# ReflowController_v1_1.net
KiCad netlist of a schematic drawn in EAGLE
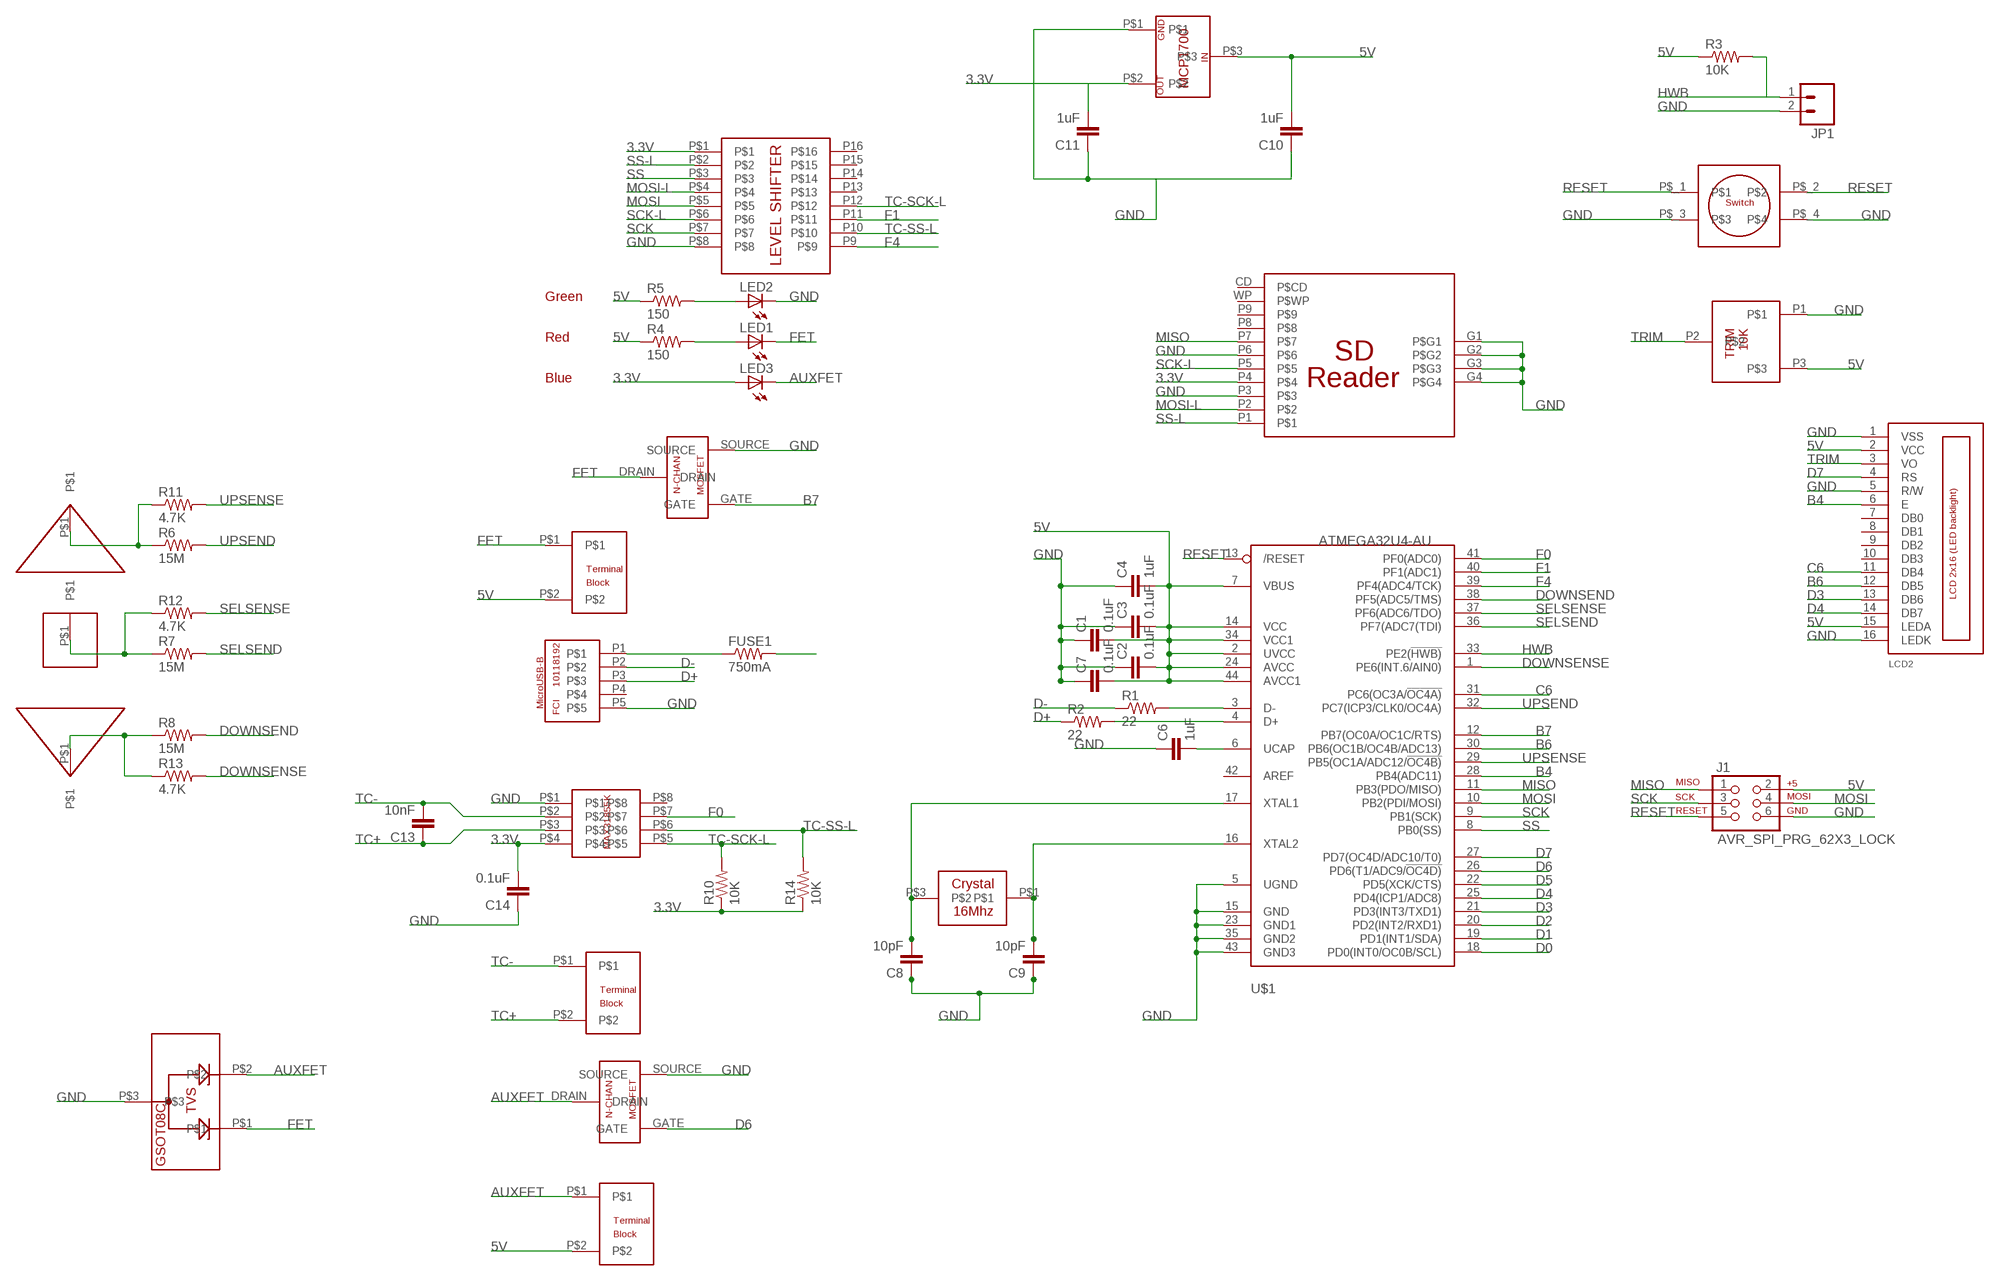
[diagram p0: schematic, sheet 1]

(export (version "E")
  (design (tool "Eeschema 10.0.6"))
  (components
    (comp (ref "C1")
      (value "0.1uF")
      (footprint "eagle-import:0603-CAP")
      (libsource (lib "eagle-import") (part "CAP0603-CAP"))
    )
    (comp (ref "C2")
      (value "0.1uF")
      (footprint "eagle-import:0603-CAP")
      (libsource (lib "eagle-import") (part "CAP0603-CAP"))
    )
    (comp (ref "C3")
      (value "0.1uF")
      (footprint "eagle-import:0603-CAP")
      (libsource (lib "eagle-import") (part "CAP0603-CAP"))
    )
    (comp (ref "C4")
      (value "1uF")
      (footprint "eagle-import:0603-CAP")
      (libsource (lib "eagle-import") (part "CAP0603-CAP"))
    )
    (comp (ref "C6")
      (value "1uF")
      (footprint "eagle-import:0603-CAP")
      (libsource (lib "eagle-import") (part "CAP0603-CAP"))
    )
    (comp (ref "C7")
      (value "0.1uF")
      (footprint "eagle-import:0603-CAP")
      (libsource (lib "eagle-import") (part "CAP0603-CAP"))
    )
    (comp (ref "C8")
      (value "10pF")
      (footprint "eagle-import:0603-CAP")
      (libsource (lib "eagle-import") (part "CAP0603-CAP"))
    )
    (comp (ref "C9")
      (value "10pF")
      (footprint "eagle-import:0603-CAP")
      (libsource (lib "eagle-import") (part "CAP0603-CAP"))
    )
    (comp (ref "C10")
      (value "1uF")
      (footprint "eagle-import:0603-CAP")
      (libsource (lib "eagle-import") (part "CAP0603-CAP"))
    )
    (comp (ref "C11")
      (value "1uF")
      (footprint "eagle-import:0603-CAP")
      (libsource (lib "eagle-import") (part "CAP0603-CAP"))
    )
    (comp (ref "C13")
      (value "10nF")
      (footprint "eagle-import:0603-CAP")
      (libsource (lib "eagle-import") (part "CAP0603-CAP"))
    )
    (comp (ref "C14")
      (value "0.1uF")
      (footprint "eagle-import:0603-CAP")
      (libsource (lib "eagle-import") (part "CAP0603-CAP"))
    )
    (comp (ref "FUSE1")
      (value "750mA")
      (footprint "eagle-import:0603-RES")
      (libsource (lib "eagle-import") (part "RESISTOR0603-RES"))
    )
    (comp (ref "J1")
      (value "AVR_SPI_PRG_62X3_LOCK")
      (footprint "eagle-import:2X3_LOCK")
      (libsource (lib "eagle-import") (part "AVR_SPI_PRG_62X3_LOCK"))
    )
    (comp (ref "JP1")
      (value "M02PTH")
      (footprint "eagle-import:1X02")
      (libsource (lib "eagle-import") (part "M02PTH"))
    )
    (comp (ref "LCD2")
      (value "LCD_2X16_SIL")
      (footprint "eagle-import:HY-1602F")
      (libsource (lib "eagle-import") (part "LCD_2X16_SIL"))
    )
    (comp (ref "LED1")
      (value "LED0603")
      (footprint "eagle-import:LED-0603")
      (libsource (lib "eagle-import") (part "LED0603"))
    )
    (comp (ref "LED2")
      (value "LED0603")
      (footprint "eagle-import:LED-0603")
      (libsource (lib "eagle-import") (part "LED0603"))
    )
    (comp (ref "LED3")
      (value "LED0603")
      (footprint "eagle-import:LED-0603")
      (libsource (lib "eagle-import") (part "LED0603"))
    )
    (comp (ref "R1")
      (value "22")
      (footprint "eagle-import:0603-RES")
      (libsource (lib "eagle-import") (part "RESISTOR0603-RES"))
    )
    (comp (ref "R2")
      (value "22")
      (footprint "eagle-import:0603-RES")
      (libsource (lib "eagle-import") (part "RESISTOR0603-RES"))
    )
    (comp (ref "R3")
      (value "10K")
      (footprint "eagle-import:0603-RES")
      (libsource (lib "eagle-import") (part "RESISTOR0603-RES"))
    )
    (comp (ref "R4")
      (value "150")
      (footprint "eagle-import:0603-RES")
      (libsource (lib "eagle-import") (part "RESISTOR0603-RES"))
    )
    (comp (ref "R5")
      (value "150")
      (footprint "eagle-import:0603-RES")
      (libsource (lib "eagle-import") (part "RESISTOR0603-RES"))
    )
    (comp (ref "R6")
      (value "15M")
      (footprint "eagle-import:0603-RES")
      (libsource (lib "eagle-import") (part "RESISTOR0603-RES"))
    )
    (comp (ref "R7")
      (value "15M")
      (footprint "eagle-import:0603-RES")
      (libsource (lib "eagle-import") (part "RESISTOR0603-RES"))
    )
    (comp (ref "R8")
      (value "15M")
      (footprint "eagle-import:0603-RES")
      (libsource (lib "eagle-import") (part "RESISTOR0603-RES"))
    )
    (comp (ref "R10")
      (value "10K")
      (footprint "eagle-import:0603-RES")
      (libsource (lib "eagle-import") (part "RESISTOR0603-RES"))
    )
    (comp (ref "R11")
      (value "4.7K")
      (footprint "eagle-import:0603-RES")
      (libsource (lib "eagle-import") (part "RESISTOR0603-RES"))
    )
    (comp (ref "R12")
      (value "4.7K")
      (footprint "eagle-import:0603-RES")
      (libsource (lib "eagle-import") (part "RESISTOR0603-RES"))
    )
    (comp (ref "R13")
      (value "4.7K")
      (footprint "eagle-import:0603-RES")
      (libsource (lib "eagle-import") (part "RESISTOR0603-RES"))
    )
    (comp (ref "R14")
      (value "10K")
      (footprint "eagle-import:0603-RES")
      (libsource (lib "eagle-import") (part "RESISTOR0603-RES"))
    )
    (comp (ref "U$1")
      (value "ATMEGA32U4-AU")
      (footprint "eagle-import:TQFP44")
      (libsource (lib "eagle-import") (part "ATMEGA32U4-AU"))
    )
    (comp (ref "U$2")
      (value "16MHZ-CRYSTAL_NX3225GA-16.000M-STD-CRG-1")
      (footprint "eagle-import:16MHZ-CRYSTAL_NX3225GA-16.000M-STD-CRG-1")
      (libsource (lib "eagle-import") (part "16MHZ-CRYSTAL_NX3225GA-16.000M-STD-CRG-1"))
    )
    (comp (ref "U$3")
      (value "USB-B_10118192-0001LF")
      (footprint "eagle-import:USB-B_10118192-0001LF")
      (libsource (lib "eagle-import") (part "USB-B_10118192-0001LF"))
    )
    (comp (ref "U$4")
      (value "SDREADER_2041021-4")
      (footprint "eagle-import:SDREADER_2041021-4")
      (libsource (lib "eagle-import") (part "SDREADER_2041021-4"))
    )
    (comp (ref "U$5")
      (value "2POS_TERM_ED2748-ND")
      (footprint "eagle-import:2POS_TERM_ED2748-ND")
      (libsource (lib "eagle-import") (part "2POS_TERM_ED2748-ND"))
    )
    (comp (ref "U$6")
      (value "N-MOSFET630_DMG1012T-7DICT-ND")
      (footprint "eagle-import:N-MOSFET630_DMG1012T-7DICT-ND")
      (libsource (lib "eagle-import") (part "N-MOSFET630_DMG1012T-7DICT-ND"))
    )
    (comp (ref "U$7")
      (value "2POS_TERM_ED2748-ND")
      (footprint "eagle-import:2POS_TERM_ED2748-ND")
      (libsource (lib "eagle-import") (part "2POS_TERM_ED2748-ND"))
    )
    (comp (ref "U$8")
      (value "NXP_LVL_SHIFT_74HC4050D,653")
      (footprint "eagle-import:NXP_LVL_SHIFT_74HC4050D,653")
      (libsource (lib "eagle-import") (part "NXP_LVL_SHIFT_74HC4050D,653"))
    )
    (comp (ref "U$9")
      (value "MAX_TC_MAX31855KASA+")
      (footprint "eagle-import:MAX_TC_MAX31855KASA+")
      (libsource (lib "eagle-import") (part "MAX_TC_MAX31855KASA+"))
    )
    (comp (ref "U$10")
      (value "10K_TRIM_3362F-1-103LF")
      (footprint "eagle-import:10K_TRIM_3362F-1-103LF")
      (libsource (lib "eagle-import") (part "10K_TRIM_3362F-1-103LF"))
    )
    (comp (ref "U$11")
      (value "MCP1700__LDO")
      (footprint "eagle-import:MCP1700__LDO")
      (libsource (lib "eagle-import") (part "MCP1700__LDO"))
    )
    (comp (ref "U$12")
      (value "MOM-SWITCH-EG4620CT-ND")
      (footprint "eagle-import:MOM-SWITCH-EG4620CT-ND")
      (libsource (lib "eagle-import") (part "MOM-SWITCH-EG4620CT-ND"))
    )
    (comp (ref "U$13")
      (value "CAPTOUCH_ARROW")
      (footprint "eagle-import:CAPTOUCH_ARROW")
      (libsource (lib "eagle-import") (part "CAPTOUCH_ARROW"))
    )
    (comp (ref "U$14")
      (value "CAPTOUCH_ARROW")
      (footprint "eagle-import:CAPTOUCH_ARROW")
      (libsource (lib "eagle-import") (part "CAPTOUCH_ARROW"))
    )
    (comp (ref "U$15")
      (value "CAPTOUCH_SQUARE")
      (footprint "eagle-import:CAPTOUCH_SQUARE")
      (libsource (lib "eagle-import") (part "CAPTOUCH_SQUARE"))
    )
    (comp (ref "U$16")
      (value "N-MOSFET630_DMG1012T-7DICT-ND")
      (footprint "eagle-import:N-MOSFET630_DMG1012T-7DICT-ND")
      (libsource (lib "eagle-import") (part "N-MOSFET630_DMG1012T-7DICT-ND"))
    )
    (comp (ref "U$17")
      (value "2POS_TERM_ED2748-ND")
      (footprint "eagle-import:2POS_TERM_ED2748-ND")
      (libsource (lib "eagle-import") (part "2POS_TERM_ED2748-ND"))
    )
    (comp (ref "U$18")
      (value "TVS_DIODE_MATRIX_GSOT08C-GS08")
      (footprint "eagle-import:TVS_DIODE_MATRIX_GSOT08C-GS08")
      (libsource (lib "eagle-import") (part "TVS_DIODE_MATRIX_GSOT08C-GS08"))
    )
  )
  (nets
    (net (code "1") (name "/3.3V") (class "Default")
      (node (ref "C11") (pin "2") (pinfunction "2_2") (pintype "passive"))
      (node (ref "C14") (pin "2") (pinfunction "2_2") (pintype "passive"))
      (node (ref "LED3") (pin "A") (pinfunction "A_A") (pintype "passive"))
      (node (ref "R10") (pin "1") (pinfunction "1_1") (pintype "passive"))
      (node (ref "R14") (pin "1") (pinfunction "1_1") (pintype "passive"))
      (node (ref "U$11") (pin "P$2") (pinfunction "P$2_P$2") (pintype "bidirectional"))
      (node (ref "U$4") (pin "P4") (pinfunction "P$4_P4") (pintype "bidirectional"))
      (node (ref "U$8") (pin "P$1") (pinfunction "P$1_P$1") (pintype "bidirectional"))
      (node (ref "U$9") (pin "P$4") (pinfunction "P$4_P$4") (pintype "bidirectional"))
    )
    (net (code "2") (name "/5V") (class "Default")
      (node (ref "C1") (pin "2") (pinfunction "2_2") (pintype "passive"))
      (node (ref "C10") (pin "2") (pinfunction "2_2") (pintype "passive"))
      (node (ref "C2") (pin "2") (pinfunction "2_2") (pintype "passive"))
      (node (ref "C3") (pin "2") (pinfunction "2_2") (pintype "passive"))
      (node (ref "C4") (pin "2") (pinfunction "2_2") (pintype "passive"))
      (node (ref "C7") (pin "2") (pinfunction "2_2") (pintype "passive"))
      (node (ref "FUSE1") (pin "2") (pinfunction "2_2") (pintype "passive"))
      (node (ref "J1") (pin "2") (pinfunction "2_2") (pintype "passive"))
      (node (ref "LCD2") (pin "15") (pinfunction "LEDA_15") (pintype "passive"))
      (node (ref "LCD2") (pin "2") (pinfunction "VCC_2") (pintype "power_in"))
      (node (ref "R3") (pin "1") (pinfunction "1_1") (pintype "passive"))
      (node (ref "R4") (pin "1") (pinfunction "1_1") (pintype "passive"))
      (node (ref "R5") (pin "1") (pinfunction "1_1") (pintype "passive"))
      (node (ref "U$1") (pin "14") (pinfunction "VCC_14") (pintype "bidirectional"))
      (node (ref "U$1") (pin "2") (pinfunction "UVCC_2") (pintype "bidirectional"))
      (node (ref "U$1") (pin "24") (pinfunction "AVCC_24") (pintype "bidirectional"))
      (node (ref "U$1") (pin "34") (pinfunction "VCC1_34") (pintype "bidirectional"))
      (node (ref "U$1") (pin "44") (pinfunction "AVCC1_44") (pintype "bidirectional"))
      (node (ref "U$1") (pin "7") (pinfunction "VBUS_7") (pintype "bidirectional"))
      (node (ref "U$10") (pin "P3") (pinfunction "P$3_P3") (pintype "bidirectional"))
      (node (ref "U$11") (pin "P$3") (pinfunction "P$3_P$3") (pintype "bidirectional"))
      (node (ref "U$17") (pin "P$2") (pinfunction "P$2_P$2") (pintype "bidirectional"))
      (node (ref "U$5") (pin "P$2") (pinfunction "P$2_P$2") (pintype "bidirectional"))
    )
    (net (code "3") (name "/AUXFET") (class "Default")
      (node (ref "LED3") (pin "C") (pinfunction "C_C") (pintype "passive"))
      (node (ref "U$16") (pin "DRAIN") (pinfunction "DRAIN_DRAIN") (pintype "bidirectional"))
      (node (ref "U$17") (pin "P$1") (pinfunction "P$1_P$1") (pintype "bidirectional"))
      (node (ref "U$18") (pin "P$2") (pinfunction "P$2_P$2") (pintype "bidirectional"))
    )
    (net (code "4") (name "/B4") (class "Default")
      (node (ref "LCD2") (pin "6") (pinfunction "E_6") (pintype "input"))
      (node (ref "U$1") (pin "28") (pinfunction "PB4(ADC11)_28") (pintype "bidirectional"))
    )
    (net (code "5") (name "/B6") (class "Default")
      (node (ref "LCD2") (pin "12") (pinfunction "DB5_12") (pintype "bidirectional"))
      (node (ref "U$1") (pin "30") (pinfunction "PB6(OC1B/OC4B/ADC13)_30") (pintype "bidirectional"))
    )
    (net (code "6") (name "/B7") (class "Default")
      (node (ref "U$1") (pin "12") (pinfunction "PB7(OC0A/OC1C/RTS)_12") (pintype "bidirectional"))
      (node (ref "U$6") (pin "GATE") (pinfunction "GATE_GATE") (pintype "bidirectional"))
    )
    (net (code "7") (name "/C6") (class "Default")
      (node (ref "LCD2") (pin "11") (pinfunction "DB4_11") (pintype "bidirectional"))
      (node (ref "U$1") (pin "31") (pinfunction "PC6(OC3A/~{OC4A})_31") (pintype "bidirectional"))
    )
    (net (code "8") (name "/D+") (class "Default")
      (node (ref "R2") (pin "1") (pinfunction "1_1") (pintype "passive"))
      (node (ref "U$3") (pin "P3") (pinfunction "P$3_P3") (pintype "bidirectional"))
    )
    (net (code "9") (name "/D-") (class "Default")
      (node (ref "R1") (pin "1") (pinfunction "1_1") (pintype "passive"))
      (node (ref "U$3") (pin "P2") (pinfunction "P$2_P2") (pintype "bidirectional"))
    )
    (net (code "10") (name "/D0") (class "Default")
      (node (ref "U$1") (pin "18") (pinfunction "PD0(INT0/OC0B/SCL)_18") (pintype "bidirectional"))
    )
    (net (code "11") (name "/D1") (class "Default")
      (node (ref "U$1") (pin "19") (pinfunction "PD1(INT1/SDA)_19") (pintype "bidirectional"))
    )
    (net (code "12") (name "/D2") (class "Default")
      (node (ref "U$1") (pin "20") (pinfunction "PD2(INT2/RXD1)_20") (pintype "bidirectional"))
    )
    (net (code "13") (name "/D3") (class "Default")
      (node (ref "LCD2") (pin "13") (pinfunction "DB6_13") (pintype "bidirectional"))
      (node (ref "U$1") (pin "21") (pinfunction "PD3(INT3/TXD1)_21") (pintype "bidirectional"))
    )
    (net (code "14") (name "/D4") (class "Default")
      (node (ref "LCD2") (pin "14") (pinfunction "DB7_14") (pintype "bidirectional"))
      (node (ref "U$1") (pin "25") (pinfunction "PD4(ICP1/ADC8)_25") (pintype "bidirectional"))
    )
    (net (code "15") (name "/D5") (class "Default")
      (node (ref "U$1") (pin "22") (pinfunction "PD5(XCK/CTS)_22") (pintype "bidirectional"))
    )
    (net (code "16") (name "/D6") (class "Default")
      (node (ref "U$1") (pin "26") (pinfunction "PD6(T1/ADC9/~{OC4D})_26") (pintype "bidirectional"))
      (node (ref "U$16") (pin "GATE") (pinfunction "GATE_GATE") (pintype "bidirectional"))
    )
    (net (code "17") (name "/D7") (class "Default")
      (node (ref "LCD2") (pin "4") (pinfunction "RS_4") (pintype "input"))
      (node (ref "U$1") (pin "27") (pinfunction "PD7(OC4D/ADC10/T0)_27") (pintype "bidirectional"))
    )
    (net (code "18") (name "/DOWNSEND") (class "Default")
      (node (ref "R8") (pin "2") (pinfunction "2_2") (pintype "passive"))
      (node (ref "U$1") (pin "38") (pinfunction "PF5(ADC5/TMS)_38") (pintype "bidirectional"))
    )
    (net (code "19") (name "/DOWNSENSE") (class "Default")
      (node (ref "R13") (pin "2") (pinfunction "2_2") (pintype "passive"))
      (node (ref "U$1") (pin "1") (pinfunction "PE6(INT.6/AIN0)_1") (pintype "bidirectional"))
    )
    (net (code "20") (name "/F0") (class "Default")
      (node (ref "U$1") (pin "41") (pinfunction "PF0(ADC0)_41") (pintype "bidirectional"))
      (node (ref "U$9") (pin "P$7") (pinfunction "P$7_P$7") (pintype "bidirectional"))
    )
    (net (code "21") (name "/F1") (class "Default")
      (node (ref "U$1") (pin "40") (pinfunction "PF1(ADC1)_40") (pintype "bidirectional"))
      (node (ref "U$8") (pin "P11") (pinfunction "P$11_P11") (pintype "bidirectional"))
    )
    (net (code "22") (name "/F4") (class "Default")
      (node (ref "U$1") (pin "39") (pinfunction "PF4(ADC4/TCK)_39") (pintype "bidirectional"))
      (node (ref "U$8") (pin "P9") (pinfunction "P$9_P9") (pintype "bidirectional"))
    )
    (net (code "23") (name "/FET") (class "Default")
      (node (ref "LED1") (pin "C") (pinfunction "C_C") (pintype "passive"))
      (node (ref "U$18") (pin "P$1") (pinfunction "P$1_P$1") (pintype "bidirectional"))
      (node (ref "U$5") (pin "P$1") (pinfunction "P$1_P$1") (pintype "bidirectional"))
      (node (ref "U$6") (pin "DRAIN") (pinfunction "DRAIN_DRAIN") (pintype "bidirectional"))
    )
    (net (code "24") (name "/GND") (class "Default")
      (node (ref "C1") (pin "1") (pinfunction "1_1") (pintype "passive"))
      (node (ref "C10") (pin "1") (pinfunction "1_1") (pintype "passive"))
      (node (ref "C11") (pin "1") (pinfunction "1_1") (pintype "passive"))
      (node (ref "C14") (pin "1") (pinfunction "1_1") (pintype "passive"))
      (node (ref "C2") (pin "1") (pinfunction "1_1") (pintype "passive"))
      (node (ref "C3") (pin "1") (pinfunction "1_1") (pintype "passive"))
      (node (ref "C4") (pin "1") (pinfunction "1_1") (pintype "passive"))
      (node (ref "C6") (pin "1") (pinfunction "1_1") (pintype "passive"))
      (node (ref "C7") (pin "1") (pinfunction "1_1") (pintype "passive"))
      (node (ref "C8") (pin "1") (pinfunction "1_1") (pintype "passive"))
      (node (ref "C9") (pin "1") (pinfunction "1_1") (pintype "passive"))
      (node (ref "J1") (pin "6") (pinfunction "6_6") (pintype "passive"))
      (node (ref "JP1") (pin "2") (pinfunction "2_2") (pintype "passive"))
      (node (ref "LCD2") (pin "1") (pinfunction "VSS_1") (pintype "power_in"))
      (node (ref "LCD2") (pin "16") (pinfunction "LEDK_16") (pintype "passive"))
      (node (ref "LCD2") (pin "5") (pinfunction "R/W_5") (pintype "input"))
      (node (ref "LED2") (pin "C") (pinfunction "C_C") (pintype "passive"))
      (node (ref "U$1") (pin "15") (pinfunction "GND_15") (pintype "bidirectional"))
      (node (ref "U$1") (pin "23") (pinfunction "GND1_23") (pintype "bidirectional"))
      (node (ref "U$1") (pin "35") (pinfunction "GND2_35") (pintype "bidirectional"))
      (node (ref "U$1") (pin "43") (pinfunction "GND3_43") (pintype "bidirectional"))
      (node (ref "U$1") (pin "5") (pinfunction "UGND_5") (pintype "bidirectional"))
      (node (ref "U$10") (pin "P1") (pinfunction "P$1_P1") (pintype "bidirectional"))
      (node (ref "U$11") (pin "P$1") (pinfunction "P$1_P$1") (pintype "bidirectional"))
      (node (ref "U$12") (pin "P$_3") (pinfunction "P$3_P$_3") (pintype "bidirectional"))
      (node (ref "U$12") (pin "P$_4") (pinfunction "P$4_P$_4") (pintype "bidirectional"))
      (node (ref "U$16") (pin "SOURCE") (pinfunction "SOURCE_SOURCE") (pintype "bidirectional"))
      (node (ref "U$18") (pin "P$3") (pinfunction "P$3_P$3") (pintype "bidirectional"))
      (node (ref "U$3") (pin "P5") (pinfunction "P$5_P5") (pintype "bidirectional"))
      (node (ref "U$4") (pin "G1") (pinfunction "P$G1_G1") (pintype "bidirectional"))
      (node (ref "U$4") (pin "G2") (pinfunction "P$G2_G2") (pintype "bidirectional"))
      (node (ref "U$4") (pin "G3") (pinfunction "P$G3_G3") (pintype "bidirectional"))
      (node (ref "U$4") (pin "G4") (pinfunction "P$G4_G4") (pintype "bidirectional"))
      (node (ref "U$4") (pin "P3") (pinfunction "P$3_P3") (pintype "bidirectional"))
      (node (ref "U$4") (pin "P6") (pinfunction "P$6_P6") (pintype "bidirectional"))
      (node (ref "U$6") (pin "SOURCE") (pinfunction "SOURCE_SOURCE") (pintype "bidirectional"))
      (node (ref "U$8") (pin "P$8") (pinfunction "P$8_P$8") (pintype "bidirectional"))
      (node (ref "U$9") (pin "P$1") (pinfunction "P$1_P$1") (pintype "bidirectional"))
    )
    (net (code "25") (name "/HWB") (class "Default")
      (node (ref "JP1") (pin "1") (pinfunction "1_1") (pintype "passive"))
      (node (ref "R3") (pin "2") (pinfunction "2_2") (pintype "passive"))
      (node (ref "U$1") (pin "33") (pinfunction "PE2(~{HWB})_33") (pintype "bidirectional"))
    )
    (net (code "26") (name "/MISO") (class "Default")
      (node (ref "J1") (pin "1") (pinfunction "1_1") (pintype "passive"))
      (node (ref "U$1") (pin "11") (pinfunction "PB3(PDO/MISO)_11") (pintype "bidirectional"))
      (node (ref "U$4") (pin "P7") (pinfunction "P$7_P7") (pintype "bidirectional"))
    )
    (net (code "27") (name "/MOSI") (class "Default")
      (node (ref "J1") (pin "4") (pinfunction "4_4") (pintype "passive"))
      (node (ref "U$1") (pin "10") (pinfunction "PB2(PDI/MOSI)_10") (pintype "bidirectional"))
      (node (ref "U$8") (pin "P$5") (pinfunction "P$5_P$5") (pintype "bidirectional"))
    )
    (net (code "28") (name "/MOSI-L") (class "Default")
      (node (ref "U$4") (pin "P2") (pinfunction "P$2_P2") (pintype "bidirectional"))
      (node (ref "U$8") (pin "P$4") (pinfunction "P$4_P$4") (pintype "bidirectional"))
    )
    (net (code "29") (name "/RESET") (class "Default")
      (node (ref "J1") (pin "5") (pinfunction "5_5") (pintype "passive"))
      (node (ref "U$1") (pin "13") (pinfunction "/RESET_13") (pintype "bidirectional"))
      (node (ref "U$12") (pin "P$_1") (pinfunction "P$1_P$_1") (pintype "bidirectional"))
      (node (ref "U$12") (pin "P$_2") (pinfunction "P$2_P$_2") (pintype "bidirectional"))
    )
    (net (code "30") (name "/SCK") (class "Default")
      (node (ref "J1") (pin "3") (pinfunction "3_3") (pintype "passive"))
      (node (ref "U$1") (pin "9") (pinfunction "PB1(SCK)_9") (pintype "bidirectional"))
      (node (ref "U$8") (pin "P$7") (pinfunction "P$7_P$7") (pintype "bidirectional"))
    )
    (net (code "31") (name "/SCK-L") (class "Default")
      (node (ref "U$4") (pin "P5") (pinfunction "P$5_P5") (pintype "bidirectional"))
      (node (ref "U$8") (pin "P$6") (pinfunction "P$6_P$6") (pintype "bidirectional"))
    )
    (net (code "32") (name "/SELSEND") (class "Default")
      (node (ref "R7") (pin "2") (pinfunction "2_2") (pintype "passive"))
      (node (ref "U$1") (pin "36") (pinfunction "PF7(ADC7(TDI)_36") (pintype "bidirectional"))
    )
    (net (code "33") (name "/SELSENSE") (class "Default")
      (node (ref "R12") (pin "2") (pinfunction "2_2") (pintype "passive"))
      (node (ref "U$1") (pin "37") (pinfunction "PF6(ADC6/TDO)_37") (pintype "bidirectional"))
    )
    (net (code "34") (name "/SS") (class "Default")
      (node (ref "U$1") (pin "8") (pinfunction "PB0(SS)_8") (pintype "bidirectional"))
      (node (ref "U$8") (pin "P$3") (pinfunction "P$3_P$3") (pintype "bidirectional"))
    )
    (net (code "35") (name "/SS-L") (class "Default")
      (node (ref "U$4") (pin "P1") (pinfunction "P$1_P1") (pintype "bidirectional"))
      (node (ref "U$8") (pin "P$2") (pinfunction "P$2_P$2") (pintype "bidirectional"))
    )
    (net (code "36") (name "/TC+") (class "Default")
      (node (ref "C13") (pin "1") (pinfunction "1_1") (pintype "passive"))
      (node (ref "U$7") (pin "P$2") (pinfunction "P$2_P$2") (pintype "bidirectional"))
      (node (ref "U$9") (pin "P$3") (pinfunction "P$3_P$3") (pintype "bidirectional"))
    )
    (net (code "37") (name "/TC-") (class "Default")
      (node (ref "C13") (pin "2") (pinfunction "2_2") (pintype "passive"))
      (node (ref "U$7") (pin "P$1") (pinfunction "P$1_P$1") (pintype "bidirectional"))
      (node (ref "U$9") (pin "P$2") (pinfunction "P$2_P$2") (pintype "bidirectional"))
    )
    (net (code "38") (name "/TC-SCK-L") (class "Default")
      (node (ref "R10") (pin "2") (pinfunction "2_2") (pintype "passive"))
      (node (ref "U$8") (pin "P12") (pinfunction "P$12_P12") (pintype "bidirectional"))
      (node (ref "U$9") (pin "P$5") (pinfunction "P$5_P$5") (pintype "bidirectional"))
    )
    (net (code "39") (name "/TC-SS-L") (class "Default")
      (node (ref "R14") (pin "2") (pinfunction "2_2") (pintype "passive"))
      (node (ref "U$8") (pin "P10") (pinfunction "P$10_P10") (pintype "bidirectional"))
      (node (ref "U$9") (pin "P$6") (pinfunction "P$6_P$6") (pintype "bidirectional"))
    )
    (net (code "40") (name "/TRIM") (class "Default")
      (node (ref "LCD2") (pin "3") (pinfunction "VO_3") (pintype "input"))
      (node (ref "U$10") (pin "P2") (pinfunction "P$2_P2") (pintype "bidirectional"))
    )
    (net (code "41") (name "/UPSEND") (class "Default")
      (node (ref "R6") (pin "2") (pinfunction "2_2") (pintype "passive"))
      (node (ref "U$1") (pin "32") (pinfunction "PC7(ICP3/CLK0/OC4A)_32") (pintype "bidirectional"))
    )
    (net (code "42") (name "/UPSENSE") (class "Default")
      (node (ref "R11") (pin "2") (pinfunction "2_2") (pintype "passive"))
      (node (ref "U$1") (pin "29") (pinfunction "PB5(OC1A/ADC12/~{OC4B})_29") (pintype "bidirectional"))
    )
    (net (code "43") (name "Net-(LED1-PadA)") (class "Default")
      (node (ref "LED1") (pin "A") (pinfunction "A_A") (pintype "passive"))
      (node (ref "R4") (pin "2") (pinfunction "2_2") (pintype "passive"))
    )
    (net (code "44") (name "Net-(LED2-PadA)") (class "Default")
      (node (ref "LED2") (pin "A") (pinfunction "A_A") (pintype "passive"))
      (node (ref "R5") (pin "2") (pinfunction "2_2") (pintype "passive"))
    )
    (net (code "45") (name "Net-(R11-Pad1)") (class "Default")
      (node (ref "R11") (pin "1") (pinfunction "1_1") (pintype "passive"))
      (node (ref "R6") (pin "1") (pinfunction "1_1") (pintype "passive"))
      (node (ref "U$13") (pin "P$1") (pinfunction "P$1_P$1") (pintype "bidirectional"))
    )
    (net (code "46") (name "Net-(R12-Pad1)") (class "Default")
      (node (ref "R12") (pin "1") (pinfunction "1_1") (pintype "passive"))
      (node (ref "R7") (pin "1") (pinfunction "1_1") (pintype "passive"))
      (node (ref "U$15") (pin "P$1") (pinfunction "P$1_P$1") (pintype "bidirectional"))
    )
    (net (code "47") (name "Net-(R13-Pad1)") (class "Default")
      (node (ref "R13") (pin "1") (pinfunction "1_1") (pintype "passive"))
      (node (ref "R8") (pin "1") (pinfunction "1_1") (pintype "passive"))
      (node (ref "U$14") (pin "P$1") (pinfunction "P$1_P$1") (pintype "bidirectional"))
    )
    (net (code "48") (name "Net-(U$1-D+)") (class "Default")
      (node (ref "R2") (pin "2") (pinfunction "2_2") (pintype "passive"))
      (node (ref "U$1") (pin "4") (pinfunction "D+_4") (pintype "bidirectional"))
    )
    (net (code "49") (name "Net-(U$1-D-)") (class "Default")
      (node (ref "R1") (pin "2") (pinfunction "2_2") (pintype "passive"))
      (node (ref "U$1") (pin "3") (pinfunction "D-_3") (pintype "bidirectional"))
    )
    (net (code "50") (name "Net-(U$1-UCAP)") (class "Default")
      (node (ref "C6") (pin "2") (pinfunction "2_2") (pintype "passive"))
      (node (ref "U$1") (pin "6") (pinfunction "UCAP_6") (pintype "bidirectional"))
    )
    (net (code "51") (name "Net-(U$1-XTAL1)") (class "Default")
      (node (ref "C8") (pin "2") (pinfunction "2_2") (pintype "passive"))
      (node (ref "U$1") (pin "17") (pinfunction "XTAL1_17") (pintype "bidirectional"))
      (node (ref "U$2") (pin "P$3") (pinfunction "P$2_P$3") (pintype "bidirectional"))
    )
    (net (code "52") (name "Net-(U$1-XTAL2)") (class "Default")
      (node (ref "C9") (pin "2") (pinfunction "2_2") (pintype "passive"))
      (node (ref "U$1") (pin "16") (pinfunction "XTAL2_16") (pintype "bidirectional"))
      (node (ref "U$2") (pin "P$1") (pinfunction "P$1_P$1") (pintype "bidirectional"))
    )
    (net (code "53") (name "Net-(U$3-P$1)") (class "Default")
      (node (ref "FUSE1") (pin "1") (pinfunction "1_1") (pintype "passive"))
      (node (ref "U$3") (pin "P1") (pinfunction "P$1_P1") (pintype "bidirectional"))
    )
    (net (code "54") (name "unconnected-(LCD2-DB0-Pad7)") (class "Default")
      (node (ref "LCD2") (pin "7") (pinfunction "DB0_7") (pintype "bidirectional"))
    )
    (net (code "55") (name "unconnected-(LCD2-DB1-Pad8)") (class "Default")
      (node (ref "LCD2") (pin "8") (pinfunction "DB1_8") (pintype "bidirectional"))
    )
    (net (code "56") (name "unconnected-(LCD2-DB2-Pad9)") (class "Default")
      (node (ref "LCD2") (pin "9") (pinfunction "DB2_9") (pintype "bidirectional"))
    )
    (net (code "57") (name "unconnected-(LCD2-DB3-Pad10)") (class "Default")
      (node (ref "LCD2") (pin "10") (pinfunction "DB3_10") (pintype "bidirectional"))
    )
    (net (code "58") (name "unconnected-(U$1-AREF-Pad42)") (class "Default")
      (node (ref "U$1") (pin "42") (pinfunction "AREF_42") (pintype "bidirectional"))
    )
    (net (code "59") (name "unconnected-(U$3-P$4-PadP4)") (class "Default")
      (node (ref "U$3") (pin "P4") (pinfunction "P$4_P4") (pintype "bidirectional"))
    )
    (net (code "60") (name "unconnected-(U$4-P$8-PadP8)") (class "Default")
      (node (ref "U$4") (pin "P8") (pinfunction "P$8_P8") (pintype "bidirectional"))
    )
    (net (code "61") (name "unconnected-(U$4-P$9-PadP9)") (class "Default")
      (node (ref "U$4") (pin "P9") (pinfunction "P$9_P9") (pintype "bidirectional"))
    )
    (net (code "62") (name "unconnected-(U$4-P$CD-PadCD)") (class "Default")
      (node (ref "U$4") (pin "CD") (pinfunction "P$CD_CD") (pintype "bidirectional"))
    )
    (net (code "63") (name "unconnected-(U$4-P$WP-PadWP)") (class "Default")
      (node (ref "U$4") (pin "WP") (pinfunction "P$WP_WP") (pintype "bidirectional"))
    )
    (net (code "64") (name "unconnected-(U$8-P$13-PadP13)") (class "Default")
      (node (ref "U$8") (pin "P13") (pinfunction "P$13_P13") (pintype "bidirectional"))
    )
    (net (code "65") (name "unconnected-(U$8-P$14-PadP14)") (class "Default")
      (node (ref "U$8") (pin "P14") (pinfunction "P$14_P14") (pintype "bidirectional"))
    )
    (net (code "66") (name "unconnected-(U$8-P$15-PadP15)") (class "Default")
      (node (ref "U$8") (pin "P15") (pinfunction "P$15_P15") (pintype "bidirectional"))
    )
    (net (code "67") (name "unconnected-(U$8-P$16-PadP16)") (class "Default")
      (node (ref "U$8") (pin "P16") (pinfunction "P$16_P16") (pintype "bidirectional"))
    )
    (net (code "68") (name "unconnected-(U$9-PadP$8)") (class "Default")
      (node (ref "U$9") (pin "P$8") (pinfunction "P$8_P$8") (pintype "bidirectional"))
    )
  )
)
